# BrainA1-6Mar2015.net
KiCad netlist of a schematic drawn in EAGLE
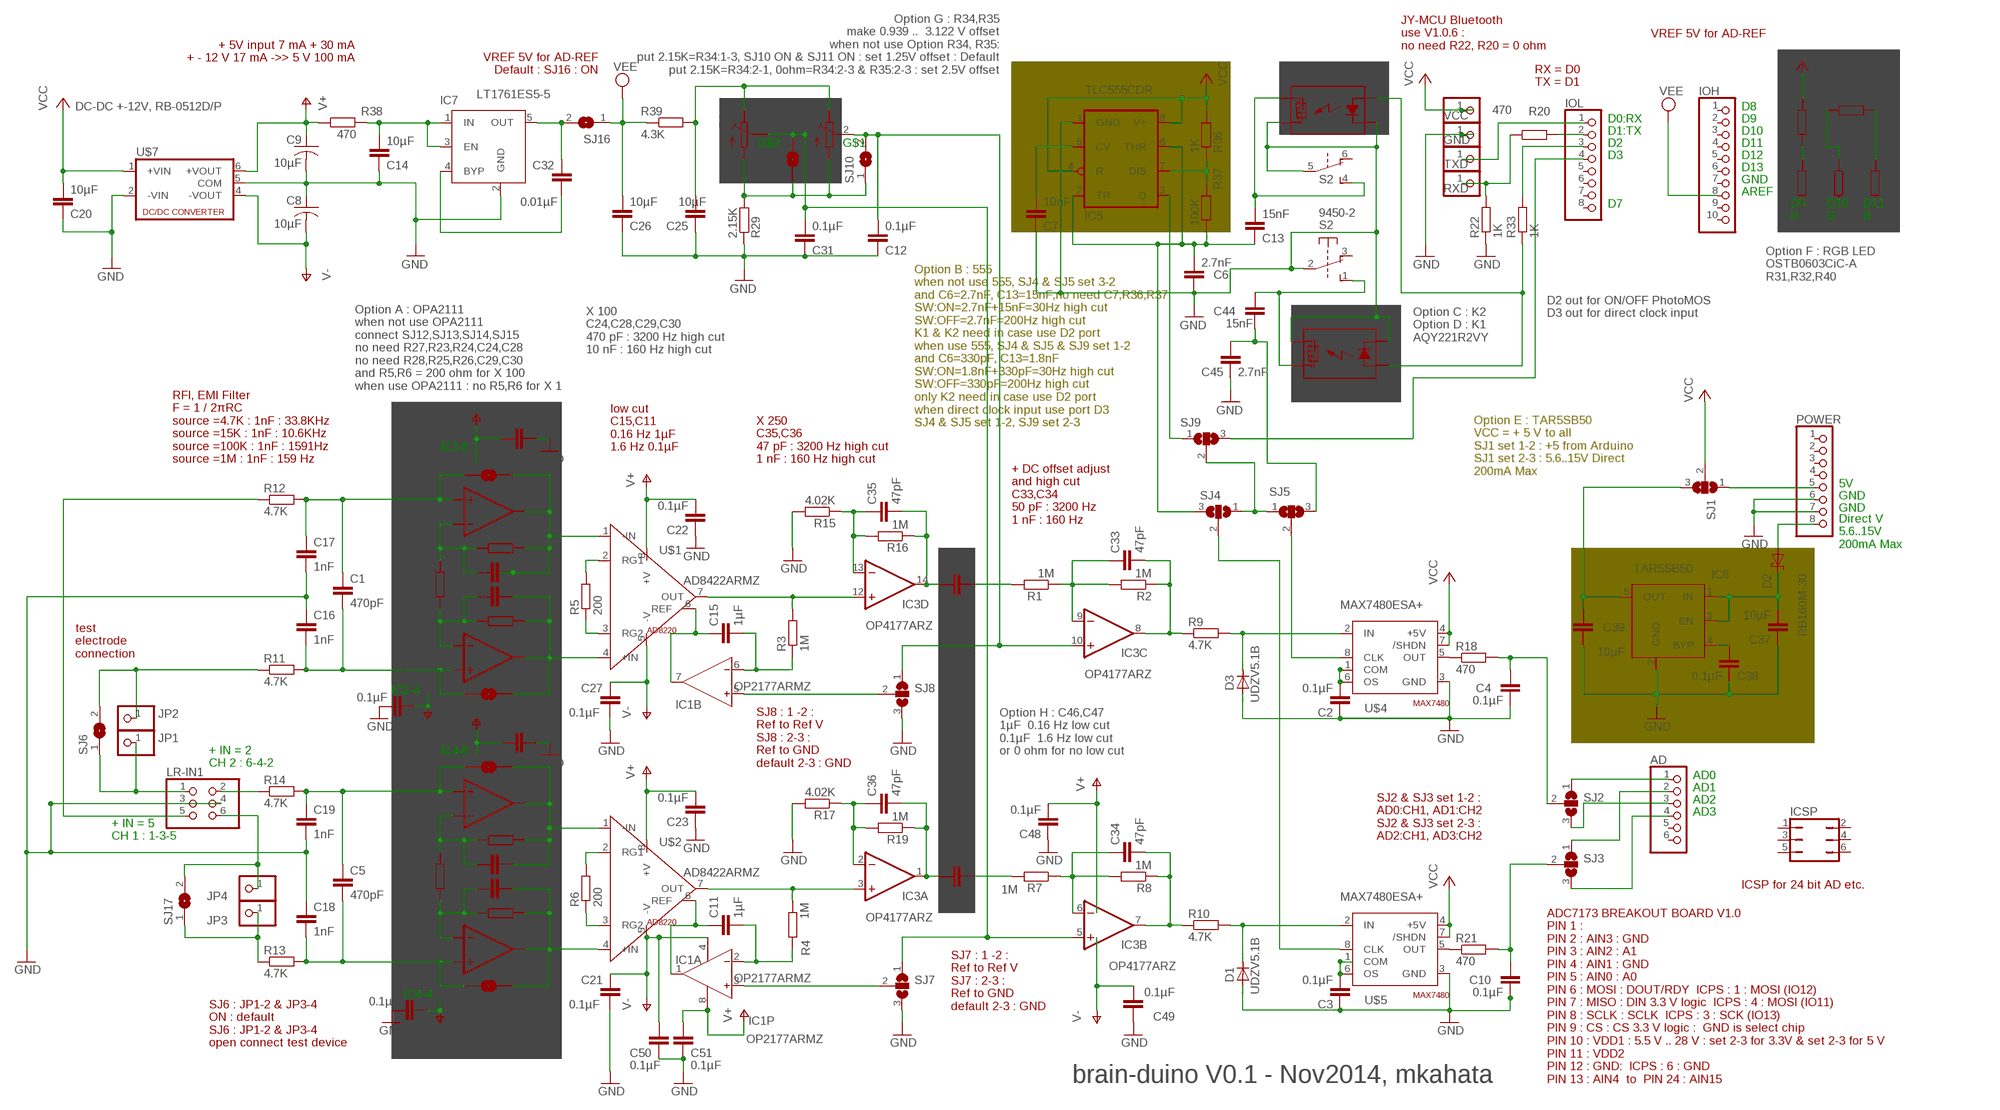
[diagram p0: schematic, sheet 1]

(export (version "E")
  (design (tool "Eeschema 10.0.6"))
  (components
    (comp (ref "AD")
      (value "PINHD-1X6")
      (footprint "eagle-import:1X06")
      (libsource (lib "eagle-import") (part "PINHD-1X6"))
    )
    (comp (ref "C1")
      (value "470pF")
      (footprint "eagle-import:C0805")
      (libsource (lib "eagle-import") (part "C-EUC0805"))
    )
    (comp (ref "C2")
      (value "0.1µF")
      (footprint "eagle-import:C0805")
      (libsource (lib "eagle-import") (part "C-EUC0805"))
    )
    (comp (ref "C3")
      (value "0.1µF")
      (footprint "eagle-import:C0805")
      (libsource (lib "eagle-import") (part "C-EUC0805"))
    )
    (comp (ref "C4")
      (value "0.1µF")
      (footprint "eagle-import:C0805")
      (libsource (lib "eagle-import") (part "C-EUC0805"))
    )
    (comp (ref "C5")
      (value "470pF")
      (footprint "eagle-import:C0805")
      (libsource (lib "eagle-import") (part "C-EUC0805"))
    )
    (comp (ref "C6")
      (value "2.7nF")
      (footprint "eagle-import:C0805")
      (libsource (lib "eagle-import") (part "C-EUC0805"))
    )
    (comp (ref "C7")
      (value "10nF")
      (footprint "eagle-import:C0805")
      (libsource (lib "eagle-import") (part "C-EUC0805"))
    )
    (comp (ref "C8")
      (value "10µF")
      (footprint "eagle-import:C0805")
      (libsource (lib "eagle-import") (part "C-USC0805"))
    )
    (comp (ref "C9")
      (value "10µF")
      (footprint "eagle-import:C0805")
      (libsource (lib "eagle-import") (part "C-USC0805"))
    )
    (comp (ref "C10")
      (value "0.1µF")
      (footprint "eagle-import:C0805")
      (libsource (lib "eagle-import") (part "C-EUC0805"))
    )
    (comp (ref "C11")
      (value "1µF")
      (footprint "eagle-import:C0805")
      (libsource (lib "eagle-import") (part "C-EUC0805"))
    )
    (comp (ref "C12")
      (value "0.1µF")
      (footprint "eagle-import:C0805")
      (libsource (lib "eagle-import") (part "C-EUC0805"))
    )
    (comp (ref "C13")
      (value "15nF")
      (footprint "eagle-import:C0805")
      (libsource (lib "eagle-import") (part "C-EUC0805"))
    )
    (comp (ref "C14")
      (value "10µF")
      (footprint "eagle-import:C0805")
      (libsource (lib "eagle-import") (part "C-EUC0805"))
    )
    (comp (ref "C15")
      (value "1µF")
      (footprint "eagle-import:C0805")
      (libsource (lib "eagle-import") (part "C-EUC0805"))
    )
    (comp (ref "C16")
      (value "1nF")
      (footprint "eagle-import:C0805")
      (libsource (lib "eagle-import") (part "C-EUC0805"))
    )
    (comp (ref "C17")
      (value "1nF")
      (footprint "eagle-import:C0805")
      (libsource (lib "eagle-import") (part "C-EUC0805"))
    )
    (comp (ref "C18")
      (value "1nF")
      (footprint "eagle-import:C0805")
      (libsource (lib "eagle-import") (part "C-EUC0805"))
    )
    (comp (ref "C19")
      (value "1nF")
      (footprint "eagle-import:C0805")
      (libsource (lib "eagle-import") (part "C-EUC0805"))
    )
    (comp (ref "C20")
      (value "10µF")
      (footprint "eagle-import:C0805")
      (libsource (lib "eagle-import") (part "C-EUC0805"))
    )
    (comp (ref "C21")
      (value "0.1µF")
      (footprint "eagle-import:C0805")
      (libsource (lib "eagle-import") (part "C-EUC0805"))
    )
    (comp (ref "C22")
      (value "0.1µF")
      (footprint "eagle-import:C0805")
      (libsource (lib "eagle-import") (part "C-EUC0805"))
    )
    (comp (ref "C23")
      (value "0.1µF")
      (footprint "eagle-import:C0805")
      (libsource (lib "eagle-import") (part "C-EUC0805"))
    )
    (comp (ref "C24")
      (value "470pF")
      (footprint "eagle-import:C0805")
      (libsource (lib "eagle-import") (part "C-EUC0805"))
    )
    (comp (ref "C25")
      (value "10µF")
      (footprint "eagle-import:C0805")
      (libsource (lib "eagle-import") (part "C-EUC0805"))
    )
    (comp (ref "C26")
      (value "10µF")
      (footprint "eagle-import:C0805")
      (libsource (lib "eagle-import") (part "C-EUC0805"))
    )
    (comp (ref "C27")
      (value "0.1µF")
      (footprint "eagle-import:C0805")
      (libsource (lib "eagle-import") (part "C-EUC0805"))
    )
    (comp (ref "C28")
      (value "470pF")
      (footprint "eagle-import:C0805")
      (libsource (lib "eagle-import") (part "C-EUC0805"))
    )
    (comp (ref "C29")
      (value "470pF")
      (footprint "eagle-import:C0805")
      (libsource (lib "eagle-import") (part "C-EUC0805"))
    )
    (comp (ref "C30")
      (value "470pF")
      (footprint "eagle-import:C0805")
      (libsource (lib "eagle-import") (part "C-EUC0805"))
    )
    (comp (ref "C31")
      (value "0.1µF")
      (footprint "eagle-import:C0805")
      (libsource (lib "eagle-import") (part "C-EUC0805"))
    )
    (comp (ref "C32")
      (value "0.01µF")
      (footprint "eagle-import:C0805")
      (libsource (lib "eagle-import") (part "C-EUC0805"))
    )
    (comp (ref "C33")
      (value "47pF")
      (footprint "eagle-import:C0805")
      (libsource (lib "eagle-import") (part "C-EUC0805"))
    )
    (comp (ref "C34")
      (value "47pF")
      (footprint "eagle-import:C0805")
      (libsource (lib "eagle-import") (part "C-EUC0805"))
    )
    (comp (ref "C35")
      (value "47pF")
      (footprint "eagle-import:C0805")
      (libsource (lib "eagle-import") (part "C-EUC0805"))
    )
    (comp (ref "C36")
      (value "47pF")
      (footprint "eagle-import:C0805")
      (libsource (lib "eagle-import") (part "C-EUC0805"))
    )
    (comp (ref "C37")
      (value "10µF")
      (footprint "eagle-import:C0805")
      (libsource (lib "eagle-import") (part "C-EUC0805"))
    )
    (comp (ref "C38")
      (value "0.1µF")
      (footprint "eagle-import:C0805")
      (libsource (lib "eagle-import") (part "C-EUC0805"))
    )
    (comp (ref "C39")
      (value "10µF")
      (footprint "eagle-import:C0805")
      (libsource (lib "eagle-import") (part "C-EUC0805"))
    )
    (comp (ref "C40")
      (value "0.1µF")
      (footprint "eagle-import:C0805")
      (libsource (lib "eagle-import") (part "C-EUC0805"))
    )
    (comp (ref "C41")
      (value "0.1µF")
      (footprint "eagle-import:C0805")
      (libsource (lib "eagle-import") (part "C-EUC0805"))
    )
    (comp (ref "C42")
      (value "0.1µF")
      (footprint "eagle-import:C0805")
      (libsource (lib "eagle-import") (part "C-EUC0805"))
    )
    (comp (ref "C43")
      (value "0.1µF")
      (footprint "eagle-import:C0805")
      (libsource (lib "eagle-import") (part "C-EUC0805"))
    )
    (comp (ref "C44")
      (value "15nF")
      (footprint "eagle-import:C0805")
      (libsource (lib "eagle-import") (part "C-EUC0805"))
    )
    (comp (ref "C45")
      (value "2.7nF")
      (footprint "eagle-import:C0805")
      (libsource (lib "eagle-import") (part "C-EUC0805"))
    )
    (comp (ref "C46")
      (value "1µF")
      (footprint "eagle-import:C0805")
      (libsource (lib "eagle-import") (part "C-EUC0805"))
    )
    (comp (ref "C47")
      (value "1µF")
      (footprint "eagle-import:C0805")
      (libsource (lib "eagle-import") (part "C-EUC0805"))
    )
    (comp (ref "C48")
      (value "0.1µF")
      (footprint "eagle-import:C0805")
      (libsource (lib "eagle-import") (part "C-EUC0805"))
    )
    (comp (ref "C49")
      (value "0.1µF")
      (footprint "eagle-import:C0805")
      (libsource (lib "eagle-import") (part "C-EUC0805"))
    )
    (comp (ref "C50")
      (value "0.1µF")
      (footprint "eagle-import:C0805")
      (libsource (lib "eagle-import") (part "C-EUC0805"))
    )
    (comp (ref "C51")
      (value "0.1µF")
      (footprint "eagle-import:C0805")
      (libsource (lib "eagle-import") (part "C-EUC0805"))
    )
    (comp (ref "D1")
      (value "UDZV5.1B")
      (footprint "eagle-import:SOD110-R")
      (libsource (lib "eagle-import") (part "DIODE-SOD110-R"))
    )
    (comp (ref "D2")
      (value "RB160M-30")
      (footprint "eagle-import:POWERDI323")
      (libsource (lib "eagle-import") (part "PD3S160"))
    )
    (comp (ref "D3")
      (value "UDZV5.1B")
      (footprint "eagle-import:SOD110-R")
      (libsource (lib "eagle-import") (part "DIODE-SOD110-R"))
    )
    (comp (ref "GND")
      (value "PINHD-1X1")
      (footprint "eagle-import:1X01")
      (libsource (lib "eagle-import") (part "PINHD-1X1"))
    )
    (comp (ref "IC1")
      (value "OP2177ARMZ")
      (footprint "eagle-import:MSOP08")
      (fields (field (name "MPN") "AD8656ARMZ"))
      (libsource (lib "eagle-import") (part "AD8656RM"))
    )
    (comp (ref "IC2")
      (value "OPA2111KP")
      (footprint "eagle-import:DIL08")
      (libsource (lib "eagle-import") (part "OPA2111P"))
    )
    (comp (ref "IC3")
      (value "OP4177ARZ")
      (footprint "eagle-import:SO14")
      (libsource (lib "eagle-import") (part "TL064D"))
    )
    (comp (ref "IC4")
      (value "OPA2111KP")
      (footprint "eagle-import:DIL08")
      (libsource (lib "eagle-import") (part "OPA2111P"))
    )
    (comp (ref "IC5")
      (value "TLC555CDR")
      (footprint "eagle-import:SO08")
      (libsource (lib "eagle-import") (part "555DLM"))
    )
    (comp (ref "IC6")
      (value "TAR5SB50")
      (footprint "eagle-import:SOT23-5")
      (libsource (lib "eagle-import") (part "MIC5219XX"))
    )
    (comp (ref "IC7")
      (value "LT1761ES5-5")
      (footprint "eagle-import:SOT23-5")
      (libsource (lib "eagle-import") (part "MIC5219XX"))
    )
    (comp (ref "ICSP")
      (value "JP3Q")
      (footprint "eagle-import:JP3Q")
      (libsource (lib "eagle-import") (part "JP3Q"))
    )
    (comp (ref "IOH")
      (value "PINHD-1X10")
      (footprint "eagle-import:1X10")
      (libsource (lib "eagle-import") (part "PINHD-1X10"))
    )
    (comp (ref "IOL")
      (value "PINHD-1X8")
      (footprint "eagle-import:1X08")
      (libsource (lib "eagle-import") (part "PINHD-1X8"))
    )
    (comp (ref "JP1")
      (value "PINHD-1X1")
      (footprint "eagle-import:1X01")
      (libsource (lib "eagle-import") (part "PINHD-1X1"))
    )
    (comp (ref "JP2")
      (value "PINHD-1X1")
      (footprint "eagle-import:1X01")
      (libsource (lib "eagle-import") (part "PINHD-1X1"))
    )
    (comp (ref "JP3")
      (value "PINHD-1X1")
      (footprint "eagle-import:1X01")
      (libsource (lib "eagle-import") (part "PINHD-1X1"))
    )
    (comp (ref "JP4")
      (value "PINHD-1X1")
      (footprint "eagle-import:1X01")
      (libsource (lib "eagle-import") (part "PINHD-1X1"))
    )
    (comp (ref "K1")
      (value "AQY221R2VY")
      (footprint "eagle-import:SSOP4")
      (fields (field (name "MF") "AROMAT/ MATSUSHITA") (field (name "MPN") "AQY221R2V"))
      (libsource (lib "eagle-import") (part "AQY2212VR"))
    )
    (comp (ref "K2")
      (value "AQY221R2VY")
      (footprint "eagle-import:SSOP4")
      (fields (field (name "MF") "AROMAT/ MATSUSHITA") (field (name "MPN") "AQY221R2V"))
      (libsource (lib "eagle-import") (part "AQY2212VR"))
    )
    (comp (ref "LR-IN1")
      (value "PINHD-2X3/90")
      (footprint "eagle-import:2X03_90")
      (libsource (lib "eagle-import") (part "PINHD-2X3/90"))
    )
    (comp (ref "POWER")
      (value "PINHD-1X8")
      (footprint "eagle-import:1X08")
      (libsource (lib "eagle-import") (part "PINHD-1X8"))
    )
    (comp (ref "R1")
      (value "1M")
      (footprint "eagle-import:R0805")
      (libsource (lib "eagle-import") (part "R-EU_R0805"))
    )
    (comp (ref "R2")
      (value "1M")
      (footprint "eagle-import:R0805")
      (libsource (lib "eagle-import") (part "R-EU_R0805"))
    )
    (comp (ref "R3")
      (value "1M")
      (footprint "eagle-import:R0805")
      (libsource (lib "eagle-import") (part "R-EU_R0805"))
    )
    (comp (ref "R4")
      (value "1M")
      (footprint "eagle-import:R0805")
      (libsource (lib "eagle-import") (part "R-EU_R0805"))
    )
    (comp (ref "R5")
      (value "200")
      (footprint "eagle-import:R0805")
      (libsource (lib "eagle-import") (part "R-EU_R0805"))
    )
    (comp (ref "R6")
      (value "200")
      (footprint "eagle-import:R0805")
      (libsource (lib "eagle-import") (part "R-EU_R0805"))
    )
    (comp (ref "R7")
      (value "1M")
      (footprint "eagle-import:R0805")
      (libsource (lib "eagle-import") (part "R-EU_R0805"))
    )
    (comp (ref "R8")
      (value "1M")
      (footprint "eagle-import:R0805")
      (libsource (lib "eagle-import") (part "R-EU_R0805"))
    )
    (comp (ref "R9")
      (value "4.7K")
      (footprint "eagle-import:R0805")
      (libsource (lib "eagle-import") (part "R-EU_R0805"))
    )
    (comp (ref "R10")
      (value "4.7K")
      (footprint "eagle-import:R0805")
      (libsource (lib "eagle-import") (part "R-EU_R0805"))
    )
    (comp (ref "R11")
      (value "4.7K")
      (footprint "eagle-import:R0805")
      (libsource (lib "eagle-import") (part "R-EU_R0805"))
    )
    (comp (ref "R12")
      (value "4.7K")
      (footprint "eagle-import:R0805")
      (libsource (lib "eagle-import") (part "R-EU_R0805"))
    )
    (comp (ref "R13")
      (value "4.7K")
      (footprint "eagle-import:R0805")
      (libsource (lib "eagle-import") (part "R-EU_R0805"))
    )
    (comp (ref "R14")
      (value "4.7K")
      (footprint "eagle-import:R0805")
      (libsource (lib "eagle-import") (part "R-EU_R0805"))
    )
    (comp (ref "R15")
      (value "4.02K")
      (footprint "eagle-import:R0805")
      (libsource (lib "eagle-import") (part "R-EU_R0805"))
    )
    (comp (ref "R16")
      (value "1M")
      (footprint "eagle-import:R0805")
      (libsource (lib "eagle-import") (part "R-EU_R0805"))
    )
    (comp (ref "R17")
      (value "4.02K")
      (footprint "eagle-import:R0805")
      (libsource (lib "eagle-import") (part "R-EU_R0805"))
    )
    (comp (ref "R18")
      (value "470")
      (footprint "eagle-import:R0805")
      (libsource (lib "eagle-import") (part "R-EU_R0805"))
    )
    (comp (ref "R19")
      (value "1M")
      (footprint "eagle-import:R0805")
      (libsource (lib "eagle-import") (part "R-EU_R0805"))
    )
    (comp (ref "R20")
      (value "470")
      (footprint "eagle-import:R0805")
      (libsource (lib "eagle-import") (part "R-EU_R0805"))
    )
    (comp (ref "R21")
      (value "470")
      (footprint "eagle-import:R0805")
      (libsource (lib "eagle-import") (part "R-EU_R0805"))
    )
    (comp (ref "R22")
      (value "1K")
      (footprint "eagle-import:R0805")
      (libsource (lib "eagle-import") (part "R-EU_R0805"))
    )
    (comp (ref "R23")
      (value "100K")
      (footprint "eagle-import:R0805")
      (libsource (lib "eagle-import") (part "R-EU_R0805"))
    )
    (comp (ref "R24")
      (value "100K")
      (footprint "eagle-import:R0805")
      (libsource (lib "eagle-import") (part "R-EU_R0805"))
    )
    (comp (ref "R25")
      (value "100K")
      (footprint "eagle-import:R0805")
      (libsource (lib "eagle-import") (part "R-EU_R0805"))
    )
    (comp (ref "R26")
      (value "100K")
      (footprint "eagle-import:R0805")
      (libsource (lib "eagle-import") (part "R-EU_R0805"))
    )
    (comp (ref "R27")
      (value "2K")
      (footprint "eagle-import:R0805")
      (libsource (lib "eagle-import") (part "R-EU_R0805"))
    )
    (comp (ref "R28")
      (value "2K")
      (footprint "eagle-import:R0805")
      (libsource (lib "eagle-import") (part "R-EU_R0805"))
    )
    (comp (ref "R29")
      (value "2.15K")
      (footprint "eagle-import:R0805")
      (libsource (lib "eagle-import") (part "R-EU_R0805"))
    )
    (comp (ref "R30")
      (value "LED")
      (footprint "eagle-import:R0402")
      (libsource (lib "eagle-import") (part "R-EU_R0402"))
    )
    (comp (ref "R31")
      (value "1K")
      (footprint "eagle-import:R0402")
      (libsource (lib "eagle-import") (part "R-EU_R0402"))
    )
    (comp (ref "R32")
      (value "1K")
      (footprint "eagle-import:R0402")
      (libsource (lib "eagle-import") (part "R-EU_R0402"))
    )
    (comp (ref "R33")
      (value "1K")
      (footprint "eagle-import:R0805")
      (libsource (lib "eagle-import") (part "R-EU_R0805"))
    )
    (comp (ref "R34")
      (value "10K")
      (footprint "eagle-import:RTRIM5X")
      (libsource (lib "eagle-import") (part "R-TRIMM5X"))
    )
    (comp (ref "R35")
      (value "10K")
      (footprint "eagle-import:RTRIM5X")
      (libsource (lib "eagle-import") (part "R-TRIMM5X"))
    )
    (comp (ref "R36")
      (value "1K")
      (footprint "eagle-import:R0805")
      (libsource (lib "eagle-import") (part "R-EU_R0805"))
    )
    (comp (ref "R37")
      (value "100K")
      (footprint "eagle-import:R0805")
      (libsource (lib "eagle-import") (part "R-EU_R0805"))
    )
    (comp (ref "R38")
      (value "470")
      (footprint "eagle-import:R0805")
      (libsource (lib "eagle-import") (part "R-EU_R0805"))
    )
    (comp (ref "R39")
      (value "4.3K")
      (footprint "eagle-import:R0805")
      (libsource (lib "eagle-import") (part "R-EU_R0805"))
    )
    (comp (ref "R40")
      (value "1K")
      (footprint "eagle-import:R0402")
      (libsource (lib "eagle-import") (part "R-EU_R0402"))
    )
    (comp (ref "R41")
      (value "LED")
      (footprint "eagle-import:R0402")
      (libsource (lib "eagle-import") (part "R-EU_R0402"))
    )
    (comp (ref "RXD")
      (value "PINHD-1X1")
      (footprint "eagle-import:1X01")
      (libsource (lib "eagle-import") (part "PINHD-1X1"))
    )
    (comp (ref "S2")
      (value "9450-2")
      (footprint "eagle-import:9450-2")
      (libsource (lib "eagle-import") (part "9450-2"))
    )
    (comp (ref "SJ1")
      (value "SJ2W")
      (footprint "eagle-import:SJ_2")
      (libsource (lib "eagle-import") (part "SJ2W"))
    )
    (comp (ref "SJ2")
      (value "SJ2W")
      (footprint "eagle-import:SJ_2")
      (libsource (lib "eagle-import") (part "SJ2W"))
    )
    (comp (ref "SJ3")
      (value "SJ2W")
      (footprint "eagle-import:SJ_2")
      (libsource (lib "eagle-import") (part "SJ2W"))
    )
    (comp (ref "SJ4")
      (value "SJ2W")
      (footprint "eagle-import:SJ_2")
      (libsource (lib "eagle-import") (part "SJ2W"))
    )
    (comp (ref "SJ5")
      (value "SJ2W")
      (footprint "eagle-import:SJ_2")
      (libsource (lib "eagle-import") (part "SJ2W"))
    )
    (comp (ref "SJ6") (value "SJ") (footprint "eagle-import:SJ") (libsource (lib "eagle-import") (part "SJ")))
    (comp (ref "SJ7")
      (value "SJ2W")
      (footprint "eagle-import:SJ_2")
      (libsource (lib "eagle-import") (part "SJ2W"))
    )
    (comp (ref "SJ8")
      (value "SJ2W")
      (footprint "eagle-import:SJ_2")
      (libsource (lib "eagle-import") (part "SJ2W"))
    )
    (comp (ref "SJ9")
      (value "SJ2W")
      (footprint "eagle-import:SJ_2")
      (libsource (lib "eagle-import") (part "SJ2W"))
    )
    (comp (ref "SJ10")
      (value "SJ")
      (footprint "eagle-import:SJ")
      (libsource (lib "eagle-import") (part "SJ"))
    )
    (comp (ref "SJ11")
      (value "SJ")
      (footprint "eagle-import:SJ")
      (libsource (lib "eagle-import") (part "SJ"))
    )
    (comp (ref "SJ12")
      (value "SJ")
      (footprint "eagle-import:SJ")
      (libsource (lib "eagle-import") (part "SJ"))
    )
    (comp (ref "SJ13")
      (value "SJ")
      (footprint "eagle-import:SJ")
      (libsource (lib "eagle-import") (part "SJ"))
    )
    (comp (ref "SJ14")
      (value "SJ")
      (footprint "eagle-import:SJ")
      (libsource (lib "eagle-import") (part "SJ"))
    )
    (comp (ref "SJ15")
      (value "SJ")
      (footprint "eagle-import:SJ")
      (libsource (lib "eagle-import") (part "SJ"))
    )
    (comp (ref "SJ16")
      (value "SJ")
      (footprint "eagle-import:SJ")
      (libsource (lib "eagle-import") (part "SJ"))
    )
    (comp (ref "SJ17")
      (value "SJ")
      (footprint "eagle-import:SJ")
      (libsource (lib "eagle-import") (part "SJ"))
    )
    (comp (ref "TXD")
      (value "PINHD-1X1")
      (footprint "eagle-import:1X01")
      (libsource (lib "eagle-import") (part "PINHD-1X1"))
    )
    (comp (ref "U$1")
      (value "AD8422ARMZ")
      (footprint "eagle-import:AD8220")
      (libsource (lib "eagle-import") (part "AD8220"))
    )
    (comp (ref "U$2")
      (value "AD8422ARMZ")
      (footprint "eagle-import:AD8220")
      (libsource (lib "eagle-import") (part "AD8220"))
    )
    (comp (ref "U$4")
      (value "MAX7480ESA+")
      (footprint "eagle-import:MAX7480")
      (libsource (lib "eagle-import") (part "MAX7480"))
    )
    (comp (ref "U$5")
      (value "MAX7480ESA+")
      (footprint "eagle-import:MAX7480")
      (libsource (lib "eagle-import") (part "MAX7480"))
    )
    (comp (ref "U$7")
      (value "DC-DC +-12V, RB-0512D/P")
      (footprint "eagle-import:RB-0515D")
      (libsource (lib "eagle-import") (part "RB-0515D"))
    )
    (comp (ref "VCC")
      (value "PINHD-1X1")
      (footprint "eagle-import:1X01")
      (libsource (lib "eagle-import") (part "PINHD-1X1"))
    )
  )
  (nets
    (net (code "1") (name "GND") (class "Default")
      (node (ref "C10") (pin "1") (pinfunction "1_1") (pintype "passive"))
      (node (ref "C12") (pin "1") (pinfunction "1_1") (pintype "passive"))
      (node (ref "C14") (pin "1") (pinfunction "1_1") (pintype "passive"))
      (node (ref "C16") (pin "1") (pinfunction "1_1") (pintype "passive"))
      (node (ref "C17") (pin "2") (pinfunction "2_2") (pintype "passive"))
      (node (ref "C18") (pin "1") (pinfunction "1_1") (pintype "passive"))
      (node (ref "C19") (pin "2") (pinfunction "2_2") (pintype "passive"))
      (node (ref "C2") (pin "1") (pinfunction "1_1") (pintype "passive"))
      (node (ref "C20") (pin "1") (pinfunction "1_1") (pintype "passive"))
      (node (ref "C21") (pin "2") (pinfunction "2_2") (pintype "passive"))
      (node (ref "C22") (pin "1") (pinfunction "1_1") (pintype "passive"))
      (node (ref "C23") (pin "1") (pinfunction "1_1") (pintype "passive"))
      (node (ref "C25") (pin "1") (pinfunction "1_1") (pintype "passive"))
      (node (ref "C26") (pin "1") (pinfunction "1_1") (pintype "passive"))
      (node (ref "C27") (pin "2") (pinfunction "2_2") (pintype "passive"))
      (node (ref "C3") (pin "1") (pinfunction "1_1") (pintype "passive"))
      (node (ref "C31") (pin "1") (pinfunction "1_1") (pintype "passive"))
      (node (ref "C37") (pin "1") (pinfunction "1_1") (pintype "passive"))
      (node (ref "C38") (pin "1") (pinfunction "1_1") (pintype "passive"))
      (node (ref "C39") (pin "1") (pinfunction "1_1") (pintype "passive"))
      (node (ref "C4") (pin "1") (pinfunction "1_1") (pintype "passive"))
      (node (ref "C40") (pin "1") (pinfunction "1_1") (pintype "passive"))
      (node (ref "C41") (pin "2") (pinfunction "2_2") (pintype "passive"))
      (node (ref "C42") (pin "2") (pinfunction "2_2") (pintype "passive"))
      (node (ref "C43") (pin "2") (pinfunction "2_2") (pintype "passive"))
      (node (ref "C45") (pin "1") (pinfunction "1_1") (pintype "passive"))
      (node (ref "C48") (pin "1") (pinfunction "1_1") (pintype "passive"))
      (node (ref "C49") (pin "1") (pinfunction "1_1") (pintype "passive"))
      (node (ref "C50") (pin "2") (pinfunction "2_2") (pintype "passive"))
      (node (ref "C51") (pin "2") (pinfunction "2_2") (pintype "passive"))
      (node (ref "C6") (pin "1") (pinfunction "1_1") (pintype "passive"))
      (node (ref "C7") (pin "1") (pinfunction "1_1") (pintype "passive"))
      (node (ref "C8") (pin "1") (pinfunction "1_1") (pintype "passive"))
      (node (ref "C9") (pin "2") (pinfunction "2_2") (pintype "passive"))
      (node (ref "D1") (pin "A") (pinfunction "A_A") (pintype "passive"))
      (node (ref "D3") (pin "A") (pinfunction "A_A") (pintype "passive"))
      (node (ref "GND") (pin "1") (pinfunction "1_1") (pintype "passive"))
      (node (ref "IC5") (pin "1") (pinfunction "GND_1") (pintype "power_in"))
      (node (ref "IC6") (pin "2") (pinfunction "GND_2") (pintype "power_in"))
      (node (ref "IC7") (pin "2") (pinfunction "GND_2") (pintype "power_in"))
      (node (ref "K1") (pin "2") (pinfunction "K_2") (pintype "passive"))
      (node (ref "K1") (pin "3") (pinfunction "DS2_3") (pintype "passive"))
      (node (ref "K2") (pin "2") (pinfunction "K_2") (pintype "passive"))
      (node (ref "K2") (pin "3") (pinfunction "DS2_3") (pintype "passive"))
      (node (ref "LR-IN1") (pin "3") (pinfunction "3_3") (pintype "passive"))
      (node (ref "LR-IN1") (pin "4") (pinfunction "4_4") (pintype "passive"))
      (node (ref "POWER") (pin "6") (pinfunction "6_6") (pintype "passive"))
      (node (ref "POWER") (pin "7") (pinfunction "7_7") (pintype "passive"))
      (node (ref "R15") (pin "2") (pinfunction "2_2") (pintype "passive"))
      (node (ref "R17") (pin "2") (pinfunction "2_2") (pintype "passive"))
      (node (ref "R22") (pin "1") (pinfunction "1_1") (pintype "passive"))
      (node (ref "R29") (pin "1") (pinfunction "1_1") (pintype "passive"))
      (node (ref "S2") (pin "2") (pinfunction "P_2") (pintype "passive"))
      (node (ref "S2") (pin "5") (pinfunction "P_5") (pintype "passive"))
      (node (ref "SJ7") (pin "3") (pinfunction "3_3") (pintype "passive"))
      (node (ref "SJ8") (pin "3") (pinfunction "3_3") (pintype "passive"))
      (node (ref "U$4") (pin "3") (pinfunction "GND_3") (pintype "power_in"))
      (node (ref "U$5") (pin "3") (pinfunction "GND_3") (pintype "power_in"))
      (node (ref "U$7") (pin "2") (pinfunction "-VIN_2") (pintype "passive"))
      (node (ref "U$7") (pin "5") (pinfunction "COM_5") (pintype "passive"))
    )
    (net (code "2") (name "Net-(AD-Pad1)") (class "Default")
      (node (ref "AD") (pin "1") (pinfunction "1_1") (pintype "passive"))
      (node (ref "SJ2") (pin "1") (pinfunction "1_1") (pintype "passive"))
    )
    (net (code "3") (name "Net-(AD-Pad2)") (class "Default")
      (node (ref "AD") (pin "2") (pinfunction "2_2") (pintype "passive"))
      (node (ref "SJ3") (pin "1") (pinfunction "1_1") (pintype "passive"))
    )
    (net (code "4") (name "Net-(AD-Pad3)") (class "Default")
      (node (ref "AD") (pin "3") (pinfunction "3_3") (pintype "passive"))
      (node (ref "SJ2") (pin "3") (pinfunction "3_3") (pintype "passive"))
    )
    (net (code "5") (name "Net-(AD-Pad4)") (class "Default")
      (node (ref "AD") (pin "4") (pinfunction "4_4") (pintype "passive"))
      (node (ref "SJ3") (pin "3") (pinfunction "3_3") (pintype "passive"))
    )
    (net (code "6") (name "Net-(C4-Pad2)") (class "Default")
      (node (ref "C4") (pin "2") (pinfunction "2_2") (pintype "passive"))
      (node (ref "R18") (pin "2") (pinfunction "2_2") (pintype "passive"))
      (node (ref "SJ2") (pin "2") (pinfunction "2_2") (pintype "passive"))
    )
    (net (code "7") (name "Net-(C10-Pad2)") (class "Default")
      (node (ref "C10") (pin "2") (pinfunction "2_2") (pintype "passive"))
      (node (ref "R21") (pin "2") (pinfunction "2_2") (pintype "passive"))
      (node (ref "SJ3") (pin "2") (pinfunction "2_2") (pintype "passive"))
    )
    (net (code "8") (name "Net-(C44-Pad1)") (class "Default")
      (node (ref "C44") (pin "1") (pinfunction "1_1") (pintype "passive"))
      (node (ref "C45") (pin "2") (pinfunction "2_2") (pintype "passive"))
      (node (ref "SJ5") (pin "3") (pinfunction "3_3") (pintype "passive"))
    )
    (net (code "9") (name "Net-(C46-Pad2)") (class "Default")
      (node (ref "C46") (pin "2") (pinfunction "2_2") (pintype "passive"))
      (node (ref "R1") (pin "2") (pinfunction "2_2") (pintype "passive"))
    )
    (net (code "10") (name "Net-(C47-Pad2)") (class "Default")
      (node (ref "C47") (pin "2") (pinfunction "2_2") (pintype "passive"))
      (node (ref "R7") (pin "2") (pinfunction "2_2") (pintype "passive"))
    )
    (net (code "11") (name "Net-(D2-PadA)") (class "Default")
      (node (ref "D2") (pin "A") (pinfunction "A_A") (pintype "passive"))
      (node (ref "POWER") (pin "8") (pinfunction "8_8") (pintype "passive"))
    )
    (net (code "12") (name "Net-(IC1A-IN+)") (class "Default")
      (node (ref "IC1") (pin "3") (pinfunction "IN+_3") (pintype "input"))
      (node (ref "SJ7") (pin "2") (pinfunction "2_2") (pintype "passive"))
    )
    (net (code "13") (name "Net-(IC1A-IN-)") (class "Default")
      (node (ref "C11") (pin "2") (pinfunction "2_2") (pintype "passive"))
      (node (ref "IC1") (pin "2") (pinfunction "IN-_2") (pintype "input"))
      (node (ref "R4") (pin "1") (pinfunction "1_1") (pintype "passive"))
    )
    (net (code "14") (name "Net-(IC1A-OUT)") (class "Default")
      (node (ref "C11") (pin "1") (pinfunction "1_1") (pintype "passive"))
      (node (ref "IC1") (pin "1") (pinfunction "OUT_1") (pintype "output"))
      (node (ref "U$2") (pin "6") (pinfunction "REF_6") (pintype "input"))
    )
    (net (code "15") (name "Net-(IC1B-IN+)") (class "Default")
      (node (ref "IC1") (pin "5") (pinfunction "IN+_5") (pintype "input"))
      (node (ref "SJ8") (pin "2") (pinfunction "2_2") (pintype "passive"))
    )
    (net (code "16") (name "Net-(IC1B-IN-)") (class "Default")
      (node (ref "C15") (pin "2") (pinfunction "2_2") (pintype "passive"))
      (node (ref "IC1") (pin "6") (pinfunction "IN-_6") (pintype "input"))
      (node (ref "R3") (pin "1") (pinfunction "1_1") (pintype "passive"))
    )
    (net (code "17") (name "Net-(IC1B-OUT)") (class "Default")
      (node (ref "C15") (pin "1") (pinfunction "1_1") (pintype "passive"))
      (node (ref "IC1") (pin "7") (pinfunction "OUT_7") (pintype "output"))
      (node (ref "U$1") (pin "6") (pinfunction "REF_6") (pintype "input"))
    )
    (net (code "18") (name "Net-(IC2A-+IN)") (class "Default")
      (node (ref "C1") (pin "1") (pinfunction "1_1") (pintype "passive"))
      (node (ref "C17") (pin "1") (pinfunction "1_1") (pintype "passive"))
      (node (ref "IC2") (pin "3") (pinfunction "+IN_3") (pintype "input"))
      (node (ref "R12") (pin "2") (pinfunction "2_2") (pintype "passive"))
      (node (ref "SJ12") (pin "2") (pinfunction "2_2") (pintype "passive"))
    )
    (net (code "19") (name "Net-(IC2A--IN)") (class "Default")
      (node (ref "C24") (pin "1") (pinfunction "1_1") (pintype "passive"))
      (node (ref "IC2") (pin "2") (pinfunction "-IN_2") (pintype "input"))
      (node (ref "R23") (pin "1") (pinfunction "1_1") (pintype "passive"))
      (node (ref "R27") (pin "2") (pinfunction "2_2") (pintype "passive"))
    )
    (net (code "20") (name "Net-(IC2A-OUT)") (class "Default")
      (node (ref "C24") (pin "2") (pinfunction "2_2") (pintype "passive"))
      (node (ref "IC2") (pin "1") (pinfunction "OUT_1") (pintype "output"))
      (node (ref "R23") (pin "2") (pinfunction "2_2") (pintype "passive"))
      (node (ref "SJ12") (pin "1") (pinfunction "1_1") (pintype "passive"))
      (node (ref "U$1") (pin "1") (pinfunction "-IN_1") (pintype "input"))
    )
    (net (code "21") (name "Net-(IC2B-+IN)") (class "Default")
      (node (ref "C1") (pin "2") (pinfunction "2_2") (pintype "passive"))
      (node (ref "C16") (pin "2") (pinfunction "2_2") (pintype "passive"))
      (node (ref "IC2") (pin "5") (pinfunction "+IN_5") (pintype "input"))
      (node (ref "R11") (pin "2") (pinfunction "2_2") (pintype "passive"))
      (node (ref "SJ13") (pin "2") (pinfunction "2_2") (pintype "passive"))
    )
    (net (code "22") (name "Net-(IC2B--IN)") (class "Default")
      (node (ref "C28") (pin "1") (pinfunction "1_1") (pintype "passive"))
      (node (ref "IC2") (pin "6") (pinfunction "-IN_6") (pintype "input"))
      (node (ref "R24") (pin "1") (pinfunction "1_1") (pintype "passive"))
      (node (ref "R27") (pin "1") (pinfunction "1_1") (pintype "passive"))
    )
    (net (code "23") (name "Net-(IC2B-OUT)") (class "Default")
      (node (ref "C28") (pin "2") (pinfunction "2_2") (pintype "passive"))
      (node (ref "IC2") (pin "7") (pinfunction "OUT_7") (pintype "output"))
      (node (ref "R24") (pin "2") (pinfunction "2_2") (pintype "passive"))
      (node (ref "SJ13") (pin "1") (pinfunction "1_1") (pintype "passive"))
      (node (ref "U$1") (pin "4") (pinfunction "+IN_4") (pintype "passive"))
    )
    (net (code "24") (name "Net-(IC3A-+IN)") (class "Default")
      (node (ref "IC3") (pin "3") (pinfunction "+IN_3") (pintype "input"))
      (node (ref "R4") (pin "2") (pinfunction "2_2") (pintype "passive"))
      (node (ref "U$2") (pin "7") (pinfunction "OUT_7") (pintype "input"))
    )
    (net (code "25") (name "Net-(IC3A--IN)") (class "Default")
      (node (ref "C36") (pin "1") (pinfunction "1_1") (pintype "passive"))
      (node (ref "IC3") (pin "2") (pinfunction "-IN_2") (pintype "input"))
      (node (ref "R17") (pin "1") (pinfunction "1_1") (pintype "passive"))
      (node (ref "R19") (pin "2") (pinfunction "2_2") (pintype "passive"))
    )
    (net (code "26") (name "Net-(IC3A-OUT)") (class "Default")
      (node (ref "C36") (pin "2") (pinfunction "2_2") (pintype "passive"))
      (node (ref "C47") (pin "1") (pinfunction "1_1") (pintype "passive"))
      (node (ref "IC3") (pin "1") (pinfunction "OUT_1") (pintype "output"))
      (node (ref "R19") (pin "1") (pinfunction "1_1") (pintype "passive"))
    )
    (net (code "27") (name "Net-(IC3B-+IN)") (class "Default")
      (node (ref "C31") (pin "2") (pinfunction "2_2") (pintype "passive"))
      (node (ref "IC3") (pin "5") (pinfunction "+IN_5") (pintype "input"))
      (node (ref "R34") (pin "2") (pinfunction "S_2") (pintype "passive"))
      (node (ref "SJ11") (pin "2") (pinfunction "2_2") (pintype "passive"))
      (node (ref "SJ7") (pin "1") (pinfunction "1_1") (pintype "passive"))
    )
    (net (code "28") (name "Net-(IC3B--IN)") (class "Default")
      (node (ref "C34") (pin "1") (pinfunction "1_1") (pintype "passive"))
      (node (ref "IC3") (pin "6") (pinfunction "-IN_6") (pintype "input"))
      (node (ref "R7") (pin "1") (pinfunction "1_1") (pintype "passive"))
      (node (ref "R8") (pin "2") (pinfunction "2_2") (pintype "passive"))
    )
    (net (code "29") (name "Net-(IC3B-OUT)") (class "Default")
      (node (ref "C34") (pin "2") (pinfunction "2_2") (pintype "passive"))
      (node (ref "IC3") (pin "7") (pinfunction "OUT_7") (pintype "output"))
      (node (ref "R10") (pin "1") (pinfunction "1_1") (pintype "passive"))
      (node (ref "R8") (pin "1") (pinfunction "1_1") (pintype "passive"))
    )
    (net (code "30") (name "Net-(IC3C-+IN)") (class "Default")
      (node (ref "C12") (pin "2") (pinfunction "2_2") (pintype "passive"))
      (node (ref "IC3") (pin "10") (pinfunction "+IN_10") (pintype "input"))
      (node (ref "R35") (pin "2") (pinfunction "S_2") (pintype "passive"))
      (node (ref "SJ10") (pin "2") (pinfunction "2_2") (pintype "passive"))
      (node (ref "SJ8") (pin "1") (pinfunction "1_1") (pintype "passive"))
    )
    (net (code "31") (name "Net-(IC3C--IN)") (class "Default")
      (node (ref "C33") (pin "1") (pinfunction "1_1") (pintype "passive"))
      (node (ref "IC3") (pin "9") (pinfunction "-IN_9") (pintype "input"))
      (node (ref "R1") (pin "1") (pinfunction "1_1") (pintype "passive"))
      (node (ref "R2") (pin "2") (pinfunction "2_2") (pintype "passive"))
    )
    (net (code "32") (name "Net-(IC3C-OUT)") (class "Default")
      (node (ref "C33") (pin "2") (pinfunction "2_2") (pintype "passive"))
      (node (ref "IC3") (pin "8") (pinfunction "OUT_8") (pintype "output"))
      (node (ref "R2") (pin "1") (pinfunction "1_1") (pintype "passive"))
      (node (ref "R9") (pin "1") (pinfunction "1_1") (pintype "passive"))
    )
    (net (code "33") (name "Net-(IC3D-+IN)") (class "Default")
      (node (ref "IC3") (pin "12") (pinfunction "+IN_12") (pintype "input"))
      (node (ref "R3") (pin "2") (pinfunction "2_2") (pintype "passive"))
      (node (ref "U$1") (pin "7") (pinfunction "OUT_7") (pintype "input"))
    )
    (net (code "34") (name "Net-(IC3D--IN)") (class "Default")
      (node (ref "C35") (pin "1") (pinfunction "1_1") (pintype "passive"))
      (node (ref "IC3") (pin "13") (pinfunction "-IN_13") (pintype "input"))
      (node (ref "R15") (pin "1") (pinfunction "1_1") (pintype "passive"))
      (node (ref "R16") (pin "2") (pinfunction "2_2") (pintype "passive"))
    )
    (net (code "35") (name "Net-(IC3D-OUT)") (class "Default")
      (node (ref "C35") (pin "2") (pinfunction "2_2") (pintype "passive"))
      (node (ref "C46") (pin "1") (pinfunction "1_1") (pintype "passive"))
      (node (ref "IC3") (pin "14") (pinfunction "OUT_14") (pintype "output"))
      (node (ref "R16") (pin "1") (pinfunction "1_1") (pintype "passive"))
    )
    (net (code "36") (name "Net-(IC4A-+IN)") (class "Default")
      (node (ref "C19") (pin "1") (pinfunction "1_1") (pintype "passive"))
      (node (ref "C5") (pin "1") (pinfunction "1_1") (pintype "passive"))
      (node (ref "IC4") (pin "3") (pinfunction "+IN_3") (pintype "input"))
      (node (ref "R14") (pin "2") (pinfunction "2_2") (pintype "passive"))
      (node (ref "SJ14") (pin "2") (pinfunction "2_2") (pintype "passive"))
    )
    (net (code "37") (name "Net-(IC4A--IN)") (class "Default")
      (node (ref "C29") (pin "1") (pinfunction "1_1") (pintype "passive"))
      (node (ref "IC4") (pin "2") (pinfunction "-IN_2") (pintype "input"))
      (node (ref "R25") (pin "1") (pinfunction "1_1") (pintype "passive"))
      (node (ref "R28") (pin "2") (pinfunction "2_2") (pintype "passive"))
    )
    (net (code "38") (name "Net-(IC4A-OUT)") (class "Default")
      (node (ref "C29") (pin "2") (pinfunction "2_2") (pintype "passive"))
      (node (ref "IC4") (pin "1") (pinfunction "OUT_1") (pintype "output"))
      (node (ref "R25") (pin "2") (pinfunction "2_2") (pintype "passive"))
      (node (ref "SJ14") (pin "1") (pinfunction "1_1") (pintype "passive"))
      (node (ref "U$2") (pin "1") (pinfunction "-IN_1") (pintype "input"))
    )
    (net (code "39") (name "Net-(IC4B-+IN)") (class "Default")
      (node (ref "C18") (pin "2") (pinfunction "2_2") (pintype "passive"))
      (node (ref "C5") (pin "2") (pinfunction "2_2") (pintype "passive"))
      (node (ref "IC4") (pin "5") (pinfunction "+IN_5") (pintype "input"))
      (node (ref "R13") (pin "2") (pinfunction "2_2") (pintype "passive"))
      (node (ref "SJ15") (pin "2") (pinfunction "2_2") (pintype "passive"))
    )
    (net (code "40") (name "Net-(IC4B--IN)") (class "Default")
      (node (ref "C30") (pin "1") (pinfunction "1_1") (pintype "passive"))
      (node (ref "IC4") (pin "6") (pinfunction "-IN_6") (pintype "input"))
      (node (ref "R26") (pin "1") (pinfunction "1_1") (pintype "passive"))
      (node (ref "R28") (pin "1") (pinfunction "1_1") (pintype "passive"))
    )
    (net (code "41") (name "Net-(IC4B-OUT)") (class "Default")
      (node (ref "C30") (pin "2") (pinfunction "2_2") (pintype "passive"))
      (node (ref "IC4") (pin "7") (pinfunction "OUT_7") (pintype "output"))
      (node (ref "R26") (pin "2") (pinfunction "2_2") (pintype "passive"))
      (node (ref "SJ15") (pin "1") (pinfunction "1_1") (pintype "passive"))
      (node (ref "U$2") (pin "4") (pinfunction "+IN_4") (pintype "passive"))
    )
    (net (code "42") (name "Net-(IC5-CV)") (class "Default")
      (node (ref "C7") (pin "2") (pinfunction "2_2") (pintype "passive"))
      (node (ref "IC5") (pin "5") (pinfunction "CV_5") (pintype "input"))
    )
    (net (code "43") (name "Net-(IC5-DIS)") (class "Default")
      (node (ref "IC5") (pin "7") (pinfunction "DIS_7") (pintype "input"))
      (node (ref "R36") (pin "1") (pinfunction "1_1") (pintype "passive"))
      (node (ref "R37") (pin "2") (pinfunction "2_2") (pintype "passive"))
    )
    (net (code "44") (name "Net-(IC5-Q)") (class "Default")
      (node (ref "IC5") (pin "3") (pinfunction "Q_3") (pintype "output"))
      (node (ref "SJ9") (pin "1") (pinfunction "1_1") (pintype "passive"))
    )
    (net (code "45") (name "Net-(IC5-THR)") (class "Default")
      (node (ref "C13") (pin "1") (pinfunction "1_1") (pintype "passive"))
      (node (ref "C6") (pin "2") (pinfunction "2_2") (pintype "passive"))
      (node (ref "IC5") (pin "2") (pinfunction "TR_2") (pintype "input"))
      (node (ref "IC5") (pin "6") (pinfunction "THR_6") (pintype "input"))
      (node (ref "R37") (pin "1") (pinfunction "1_1") (pintype "passive"))
      (node (ref "SJ4") (pin "3") (pinfunction "3_3") (pintype "passive"))
    )
    (net (code "46") (name "Net-(IC6-BYP)") (class "Default")
      (node (ref "C38") (pin "2") (pinfunction "2_2") (pintype "passive"))
      (node (ref "IC6") (pin "4") (pinfunction "BYP_4") (pintype "passive"))
    )
    (net (code "47") (name "Net-(IC6-EN)") (class "Default")
      (node (ref "C37") (pin "2") (pinfunction "2_2") (pintype "passive"))
      (node (ref "D2") (pin "C") (pinfunction "C_C") (pintype "passive"))
      (node (ref "IC6") (pin "1") (pinfunction "IN_1") (pintype "input"))
      (node (ref "IC6") (pin "3") (pinfunction "EN_3") (pintype "input"))
    )
    (net (code "48") (name "Net-(IC6-OUT)") (class "Default")
      (node (ref "C39") (pin "2") (pinfunction "2_2") (pintype "passive"))
      (node (ref "IC6") (pin "5") (pinfunction "OUT_5") (pintype "output"))
      (node (ref "SJ1") (pin "3") (pinfunction "3_3") (pintype "passive"))
    )
    (net (code "49") (name "Net-(IC7-BYP)") (class "Default")
      (node (ref "C32") (pin "1") (pinfunction "1_1") (pintype "passive"))
      (node (ref "IC7") (pin "4") (pinfunction "BYP_4") (pintype "passive"))
    )
    (net (code "50") (name "Net-(IC7-EN)") (class "Default")
      (node (ref "C14") (pin "2") (pinfunction "2_2") (pintype "passive"))
      (node (ref "IC7") (pin "1") (pinfunction "IN_1") (pintype "input"))
      (node (ref "IC7") (pin "3") (pinfunction "EN_3") (pintype "input"))
      (node (ref "R38") (pin "2") (pinfunction "2_2") (pintype "passive"))
    )
    (net (code "51") (name "Net-(IC7-OUT)") (class "Default")
      (node (ref "C32") (pin "2") (pinfunction "2_2") (pintype "passive"))
      (node (ref "IC7") (pin "5") (pinfunction "OUT_5") (pintype "output"))
      (node (ref "SJ16") (pin "2") (pinfunction "2_2") (pintype "passive"))
    )
    (net (code "52") (name "Net-(IOL-Pad1)") (class "Default")
      (node (ref "IOL") (pin "1") (pinfunction "1_1") (pintype "passive"))
      (node (ref "TXD") (pin "1") (pinfunction "1_1") (pintype "passive"))
    )
    (net (code "53") (name "Net-(IOL-Pad2)") (class "Default")
      (node (ref "IOL") (pin "2") (pinfunction "2_2") (pintype "passive"))
      (node (ref "R20") (pin "2") (pinfunction "2_2") (pintype "passive"))
    )
    (net (code "54") (name "Net-(IOL-Pad3)") (class "Default")
      (node (ref "IOL") (pin "3") (pinfunction "3_3") (pintype "passive"))
      (node (ref "R33") (pin "2") (pinfunction "2_2") (pintype "passive"))
    )
    (net (code "55") (name "Net-(IOL-Pad4)") (class "Default")
      (node (ref "IOL") (pin "4") (pinfunction "4_4") (pintype "passive"))
      (node (ref "SJ9") (pin "3") (pinfunction "3_3") (pintype "passive"))
    )
    (net (code "56") (name "Net-(JP1-Pad1)") (class "Default")
      (node (ref "JP1") (pin "1") (pinfunction "1_1") (pintype "passive"))
      (node (ref "LR-IN1") (pin "1") (pinfunction "1_1") (pintype "passive"))
      (node (ref "SJ6") (pin "1") (pinfunction "1_1") (pintype "passive"))
    )
    (net (code "57") (name "Net-(JP2-Pad1)") (class "Default")
      (node (ref "JP2") (pin "1") (pinfunction "1_1") (pintype "passive"))
      (node (ref "R11") (pin "1") (pinfunction "1_1") (pintype "passive"))
      (node (ref "SJ6") (pin "2") (pinfunction "2_2") (pintype "passive"))
    )
    (net (code "58") (name "Net-(JP3-Pad1)") (class "Default")
      (node (ref "JP3") (pin "1") (pinfunction "1_1") (pintype "passive"))
      (node (ref "R13") (pin "1") (pinfunction "1_1") (pintype "passive"))
      (node (ref "SJ17") (pin "1") (pinfunction "1_1") (pintype "passive"))
    )
    (net (code "59") (name "Net-(JP4-Pad1)") (class "Default")
      (node (ref "JP4") (pin "1") (pinfunction "1_1") (pintype "passive"))
      (node (ref "LR-IN1") (pin "6") (pinfunction "6_6") (pintype "passive"))
      (node (ref "SJ17") (pin "2") (pinfunction "2_2") (pintype "passive"))
    )
    (net (code "60") (name "Net-(K1-A)") (class "Default")
      (node (ref "K1") (pin "1") (pinfunction "A_1") (pintype "passive"))
      (node (ref "K2") (pin "1") (pinfunction "A_1") (pintype "passive"))
      (node (ref "R33") (pin "1") (pinfunction "1_1") (pintype "passive"))
    )
    (net (code "61") (name "Net-(K1-DS1)") (class "Default")
      (node (ref "C44") (pin "2") (pinfunction "2_2") (pintype "passive"))
      (node (ref "K1") (pin "4") (pinfunction "DS1_4") (pintype "passive"))
      (node (ref "S2") (pin "1") (pinfunction "S_1") (pintype "passive"))
    )
    (net (code "62") (name "Net-(K2-DS1)") (class "Default")
      (node (ref "C13") (pin "2") (pinfunction "2_2") (pintype "passive"))
      (node (ref "K2") (pin "4") (pinfunction "DS1_4") (pintype "passive"))
      (node (ref "S2") (pin "4") (pinfunction "S_4") (pintype "passive"))
    )
    (net (code "63") (name "Net-(LR-IN1-Pad2)") (class "Default")
      (node (ref "LR-IN1") (pin "2") (pinfunction "2_2") (pintype "passive"))
      (node (ref "R14") (pin "1") (pinfunction "1_1") (pintype "passive"))
    )
    (net (code "64") (name "Net-(LR-IN1-Pad5)") (class "Default")
      (node (ref "LR-IN1") (pin "5") (pinfunction "5_5") (pintype "passive"))
      (node (ref "R12") (pin "1") (pinfunction "1_1") (pintype "passive"))
    )
    (net (code "65") (name "Net-(POWER-Pad5)") (class "Default")
      (node (ref "POWER") (pin "5") (pinfunction "5_5") (pintype "passive"))
      (node (ref "SJ1") (pin "1") (pinfunction "1_1") (pintype "passive"))
    )
    (net (code "66") (name "Net-(R20-Pad1)") (class "Default")
      (node (ref "R20") (pin "1") (pinfunction "1_1") (pintype "passive"))
      (node (ref "R22") (pin "2") (pinfunction "2_2") (pintype "passive"))
      (node (ref "RXD") (pin "1") (pinfunction "1_1") (pintype "passive"))
    )
    (net (code "67") (name "Net-(R30-Pad1)") (class "Default")
      (node (ref "R30") (pin "1") (pinfunction "1_1") (pintype "passive"))
      (node (ref "R40") (pin "2") (pinfunction "2_2") (pintype "passive"))
    )
    (net (code "68") (name "Net-(R30-Pad2)") (class "Default")
      (node (ref "R30") (pin "2") (pinfunction "2_2") (pintype "passive"))
      (node (ref "R32") (pin "2") (pinfunction "2_2") (pintype "passive"))
    )
    (net (code "69") (name "Net-(R31-Pad2)") (class "Default")
      (node (ref "R31") (pin "2") (pinfunction "2_2") (pintype "passive"))
      (node (ref "R41") (pin "1") (pinfunction "1_1") (pintype "passive"))
    )
    (net (code "70") (name "Net-(R34-A)") (class "Default")
      (node (ref "C25") (pin "2") (pinfunction "2_2") (pintype "passive"))
      (node (ref "R34") (pin "3") (pinfunction "A_3") (pintype "passive"))
      (node (ref "R35") (pin "3") (pinfunction "A_3") (pintype "passive"))
      (node (ref "R39") (pin "2") (pinfunction "2_2") (pintype "passive"))
    )
    (net (code "71") (name "Net-(R34-E)") (class "Default")
      (node (ref "R29") (pin "2") (pinfunction "2_2") (pintype "passive"))
      (node (ref "R34") (pin "1") (pinfunction "E_1") (pintype "passive"))
      (node (ref "R35") (pin "1") (pinfunction "E_1") (pintype "passive"))
      (node (ref "SJ10") (pin "1") (pinfunction "1_1") (pintype "passive"))
      (node (ref "SJ11") (pin "1") (pinfunction "1_1") (pintype "passive"))
    )
    (net (code "72") (name "Net-(SJ4-Pad1)") (class "Default")
      (node (ref "SJ4") (pin "1") (pinfunction "1_1") (pintype "passive"))
      (node (ref "SJ5") (pin "1") (pinfunction "1_1") (pintype "passive"))
      (node (ref "SJ9") (pin "2") (pinfunction "2_2") (pintype "passive"))
    )
    (net (code "73") (name "Net-(U$1-RG1)") (class "Default")
      (node (ref "R5") (pin "2") (pinfunction "2_2") (pintype "passive"))
      (node (ref "U$1") (pin "2") (pinfunction "RG1_2") (pintype "input"))
    )
    (net (code "74") (name "Net-(U$1-RG2)") (class "Default")
      (node (ref "R5") (pin "1") (pinfunction "1_1") (pintype "passive"))
      (node (ref "U$1") (pin "3") (pinfunction "RG2_3") (pintype "input"))
    )
    (net (code "75") (name "Net-(U$2-RG1)") (class "Default")
      (node (ref "R6") (pin "2") (pinfunction "2_2") (pintype "passive"))
      (node (ref "U$2") (pin "2") (pinfunction "RG1_2") (pintype "input"))
    )
    (net (code "76") (name "Net-(U$2-RG2)") (class "Default")
      (node (ref "R6") (pin "1") (pinfunction "1_1") (pintype "passive"))
      (node (ref "U$2") (pin "3") (pinfunction "RG2_3") (pintype "input"))
    )
    (net (code "77") (name "Net-(U$4-CLK)") (class "Default")
      (node (ref "SJ5") (pin "2") (pinfunction "2_2") (pintype "passive"))
      (node (ref "U$4") (pin "8") (pinfunction "CLK_8") (pintype "input"))
    )
    (net (code "78") (name "Net-(U$4-COM)") (class "Default")
      (node (ref "C2") (pin "2") (pinfunction "2_2") (pintype "passive"))
      (node (ref "U$4") (pin "1") (pinfunction "COM_1") (pintype "input"))
      (node (ref "U$4") (pin "6") (pinfunction "OS_6") (pintype "passive"))
    )
    (net (code "79") (name "Net-(U$4-IN)") (class "Default")
      (node (ref "D3") (pin "C") (pinfunction "C_C") (pintype "passive"))
      (node (ref "R9") (pin "2") (pinfunction "2_2") (pintype "passive"))
      (node (ref "U$4") (pin "2") (pinfunction "IN_2") (pintype "input"))
    )
    (net (code "80") (name "Net-(U$4-OUT)") (class "Default")
      (node (ref "R18") (pin "1") (pinfunction "1_1") (pintype "passive"))
      (node (ref "U$4") (pin "5") (pinfunction "OUT_5") (pintype "input"))
    )
    (net (code "81") (name "Net-(U$5-CLK)") (class "Default")
      (node (ref "SJ4") (pin "2") (pinfunction "2_2") (pintype "passive"))
      (node (ref "U$5") (pin "8") (pinfunction "CLK_8") (pintype "input"))
    )
    (net (code "82") (name "Net-(U$5-COM)") (class "Default")
      (node (ref "C3") (pin "2") (pinfunction "2_2") (pintype "passive"))
      (node (ref "U$5") (pin "1") (pinfunction "COM_1") (pintype "input"))
      (node (ref "U$5") (pin "6") (pinfunction "OS_6") (pintype "passive"))
    )
    (net (code "83") (name "Net-(U$5-IN)") (class "Default")
      (node (ref "D1") (pin "C") (pinfunction "C_C") (pintype "passive"))
      (node (ref "R10") (pin "2") (pinfunction "2_2") (pintype "passive"))
      (node (ref "U$5") (pin "2") (pinfunction "IN_2") (pintype "input"))
    )
    (net (code "84") (name "Net-(U$5-OUT)") (class "Default")
      (node (ref "R21") (pin "1") (pinfunction "1_1") (pintype "passive"))
      (node (ref "U$5") (pin "5") (pinfunction "OUT_5") (pintype "input"))
    )
    (net (code "85") (name "V+") (class "Default")
      (node (ref "C22") (pin "2") (pinfunction "2_2") (pintype "passive"))
      (node (ref "C23") (pin "2") (pinfunction "2_2") (pintype "passive"))
      (node (ref "C40") (pin "2") (pinfunction "2_2") (pintype "passive"))
      (node (ref "C42") (pin "1") (pinfunction "1_1") (pintype "passive"))
      (node (ref "C48") (pin "2") (pinfunction "2_2") (pintype "passive"))
      (node (ref "C51") (pin "1") (pinfunction "1_1") (pintype "passive"))
      (node (ref "C9") (pin "1") (pinfunction "1_1") (pintype "passive"))
      (node (ref "IC1") (pin "8") (pinfunction "V+_8") (pintype "power_in"))
      (node (ref "R38") (pin "1") (pinfunction "1_1") (pintype "passive"))
      (node (ref "U$1") (pin "8") (pinfunction "+V_8") (pintype "power_in"))
      (node (ref "U$2") (pin "8") (pinfunction "+V_8") (pintype "power_in"))
      (node (ref "U$7") (pin "6") (pinfunction "+VOUT_6") (pintype "passive"))
    )
    (net (code "86") (name "V-") (class "Default")
      (node (ref "C21") (pin "1") (pinfunction "1_1") (pintype "passive"))
      (node (ref "C27") (pin "1") (pinfunction "1_1") (pintype "passive"))
      (node (ref "C41") (pin "1") (pinfunction "1_1") (pintype "passive"))
      (node (ref "C43") (pin "1") (pinfunction "1_1") (pintype "passive"))
      (node (ref "C49") (pin "2") (pinfunction "2_2") (pintype "passive"))
      (node (ref "C50") (pin "1") (pinfunction "1_1") (pintype "passive"))
      (node (ref "C8") (pin "2") (pinfunction "2_2") (pintype "passive"))
      (node (ref "IC1") (pin "4") (pinfunction "V-_4") (pintype "power_in"))
      (node (ref "U$1") (pin "5") (pinfunction "-V_5") (pintype "power_in"))
      (node (ref "U$2") (pin "5") (pinfunction "-V_5") (pintype "power_in"))
      (node (ref "U$7") (pin "4") (pinfunction "-VOUT_4") (pintype "passive"))
    )
    (net (code "87") (name "VCC") (class "Default")
      (node (ref "C20") (pin "2") (pinfunction "2_2") (pintype "passive"))
      (node (ref "IC5") (pin "4") (pinfunction "R_4") (pintype "input"))
      (node (ref "IC5") (pin "8") (pinfunction "V+_8") (pintype "power_in"))
      (node (ref "R36") (pin "2") (pinfunction "2_2") (pintype "passive"))
      (node (ref "R41") (pin "2") (pinfunction "2_2") (pintype "passive"))
      (node (ref "SJ1") (pin "2") (pinfunction "2_2") (pintype "passive"))
      (node (ref "U$4") (pin "4") (pinfunction "+5V_4") (pintype "power_in"))
      (node (ref "U$4") (pin "7") (pinfunction "/SHDN_7") (pintype "input"))
      (node (ref "U$5") (pin "4") (pinfunction "+5V_4") (pintype "power_in"))
      (node (ref "U$5") (pin "7") (pinfunction "/SHDN_7") (pintype "input"))
      (node (ref "U$7") (pin "1") (pinfunction "+VIN_1") (pintype "passive"))
      (node (ref "VCC") (pin "1") (pinfunction "1_1") (pintype "passive"))
    )
    (net (code "88") (name "VEE") (class "Default")
      (node (ref "C26") (pin "2") (pinfunction "2_2") (pintype "passive"))
      (node (ref "IOH") (pin "8") (pinfunction "8_8") (pintype "passive"))
      (node (ref "R39") (pin "1") (pinfunction "1_1") (pintype "passive"))
      (node (ref "SJ16") (pin "1") (pinfunction "1_1") (pintype "passive"))
    )
    (net (code "89") (name "unconnected-(AD-Pad5)") (class "Default")
      (node (ref "AD") (pin "5") (pinfunction "5_5") (pintype "passive"))
    )
    (net (code "90") (name "unconnected-(AD-Pad6)") (class "Default")
      (node (ref "AD") (pin "6") (pinfunction "6_6") (pintype "passive"))
    )
    (net (code "91") (name "unconnected-(ICSP-Pad1)") (class "Default")
      (node (ref "ICSP") (pin "1") (pinfunction "1_1") (pintype "passive"))
    )
    (net (code "92") (name "unconnected-(ICSP-Pad2)") (class "Default")
      (node (ref "ICSP") (pin "2") (pinfunction "2_2") (pintype "passive"))
    )
    (net (code "93") (name "unconnected-(ICSP-Pad3)") (class "Default")
      (node (ref "ICSP") (pin "3") (pinfunction "3_3") (pintype "passive"))
    )
    (net (code "94") (name "unconnected-(ICSP-Pad4)") (class "Default")
      (node (ref "ICSP") (pin "4") (pinfunction "4_4") (pintype "passive"))
    )
    (net (code "95") (name "unconnected-(ICSP-Pad5)") (class "Default")
      (node (ref "ICSP") (pin "5") (pinfunction "5_5") (pintype "passive"))
    )
    (net (code "96") (name "unconnected-(ICSP-Pad6)") (class "Default")
      (node (ref "ICSP") (pin "6") (pinfunction "6_6") (pintype "passive"))
    )
    (net (code "97") (name "unconnected-(IOH-Pad1)") (class "Default")
      (node (ref "IOH") (pin "1") (pinfunction "1_1") (pintype "passive"))
    )
    (net (code "98") (name "unconnected-(IOH-Pad2)") (class "Default")
      (node (ref "IOH") (pin "2") (pinfunction "2_2") (pintype "passive"))
    )
    (net (code "99") (name "unconnected-(IOH-Pad3)") (class "Default")
      (node (ref "IOH") (pin "3") (pinfunction "3_3") (pintype "passive"))
    )
    (net (code "100") (name "unconnected-(IOH-Pad4)") (class "Default")
      (node (ref "IOH") (pin "4") (pinfunction "4_4") (pintype "passive"))
    )
    (net (code "101") (name "unconnected-(IOH-Pad5)") (class "Default")
      (node (ref "IOH") (pin "5") (pinfunction "5_5") (pintype "passive"))
    )
    (net (code "102") (name "unconnected-(IOH-Pad6)") (class "Default")
      (node (ref "IOH") (pin "6") (pinfunction "6_6") (pintype "passive"))
    )
    (net (code "103") (name "unconnected-(IOH-Pad7)") (class "Default")
      (node (ref "IOH") (pin "7") (pinfunction "7_7") (pintype "passive"))
    )
    (net (code "104") (name "unconnected-(IOH-Pad9)") (class "Default")
      (node (ref "IOH") (pin "9") (pinfunction "9_9") (pintype "passive"))
    )
    (net (code "105") (name "unconnected-(IOH-Pad10)") (class "Default")
      (node (ref "IOH") (pin "10") (pinfunction "10_10") (pintype "passive"))
    )
    (net (code "106") (name "unconnected-(IOL-Pad5)") (class "Default")
      (node (ref "IOL") (pin "5") (pinfunction "5_5") (pintype "passive"))
    )
    (net (code "107") (name "unconnected-(IOL-Pad6)") (class "Default")
      (node (ref "IOL") (pin "6") (pinfunction "6_6") (pintype "passive"))
    )
    (net (code "108") (name "unconnected-(IOL-Pad7)") (class "Default")
      (node (ref "IOL") (pin "7") (pinfunction "7_7") (pintype "passive"))
    )
    (net (code "109") (name "unconnected-(IOL-Pad8)") (class "Default")
      (node (ref "IOL") (pin "8") (pinfunction "8_8") (pintype "passive"))
    )
    (net (code "110") (name "unconnected-(POWER-Pad1)") (class "Default")
      (node (ref "POWER") (pin "1") (pinfunction "1_1") (pintype "passive"))
    )
    (net (code "111") (name "unconnected-(POWER-Pad2)") (class "Default")
      (node (ref "POWER") (pin "2") (pinfunction "2_2") (pintype "passive"))
    )
    (net (code "112") (name "unconnected-(POWER-Pad3)") (class "Default")
      (node (ref "POWER") (pin "3") (pinfunction "3_3") (pintype "passive"))
    )
    (net (code "113") (name "unconnected-(POWER-Pad4)") (class "Default")
      (node (ref "POWER") (pin "4") (pinfunction "4_4") (pintype "passive"))
    )
    (net (code "114") (name "unconnected-(R31-Pad1)") (class "Default")
      (node (ref "R31") (pin "1") (pinfunction "1_1") (pintype "passive"))
    )
    (net (code "115") (name "unconnected-(R32-Pad1)") (class "Default")
      (node (ref "R32") (pin "1") (pinfunction "1_1") (pintype "passive"))
    )
    (net (code "116") (name "unconnected-(R40-Pad1)") (class "Default")
      (node (ref "R40") (pin "1") (pinfunction "1_1") (pintype "passive"))
    )
    (net (code "117") (name "unconnected-(S2A-O-Pad3)") (class "Default")
      (node (ref "S2") (pin "3") (pinfunction "O_3") (pintype "passive"))
    )
    (net (code "118") (name "unconnected-(S2B-O-Pad6)") (class "Default")
      (node (ref "S2") (pin "6") (pinfunction "O_6") (pintype "passive"))
    )
  )
)
